# Power.net
KiCad netlist of a schematic drawn in Altium Designer
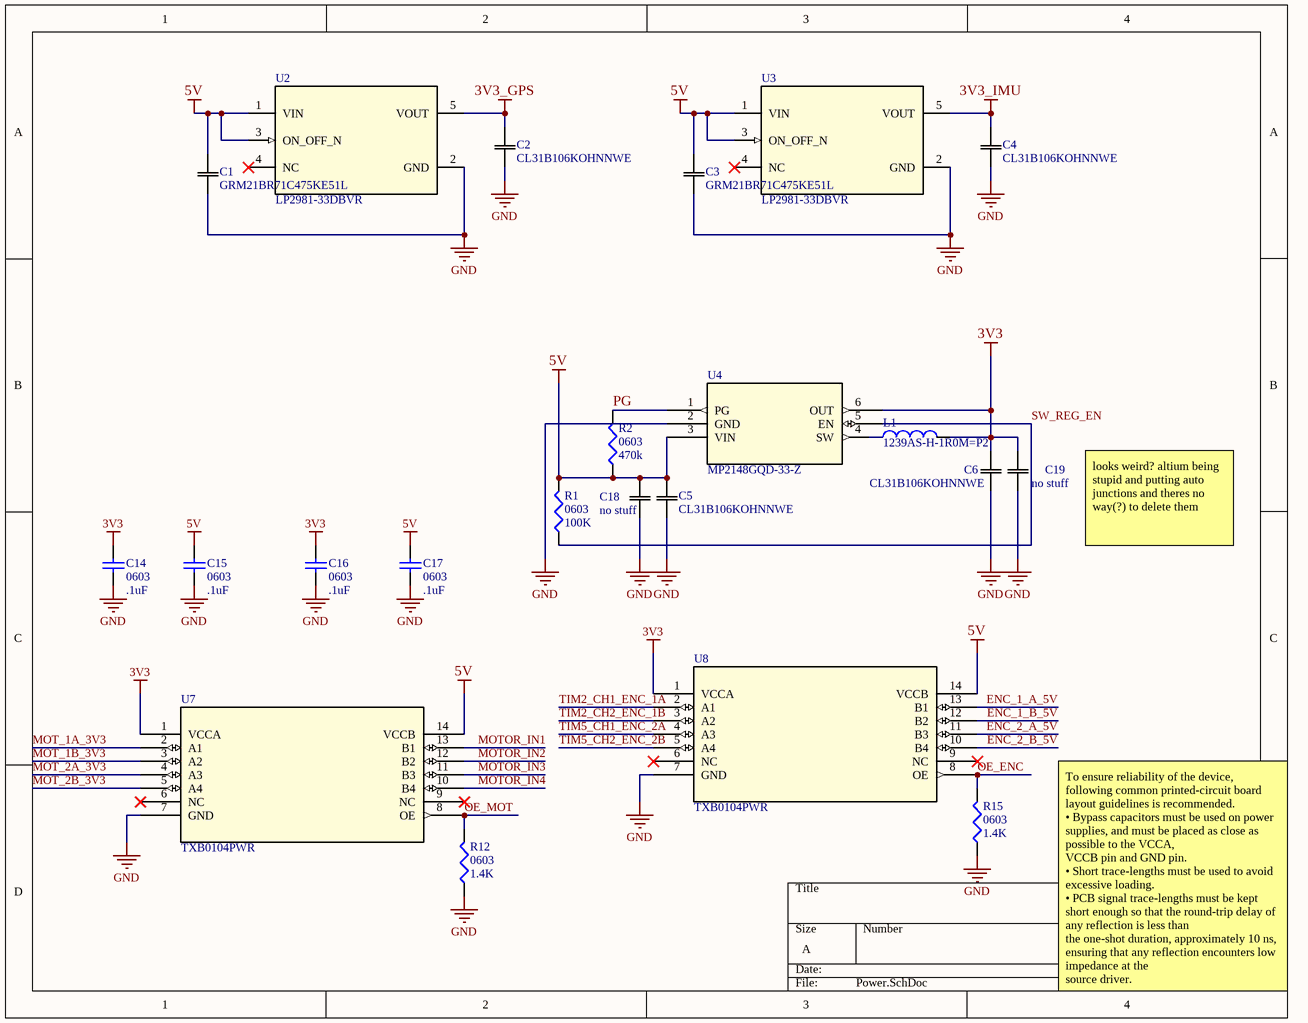
[diagram p0: Power.SchDoc]

(export (version "E")
  (design (tool "Eeschema 10.0.6"))
  (components
    (comp (ref "C1")
      (value "GRM21BR71C475KE51L")
      (footprint "swarm_crawler_pcb:CAP_GRM0805_2X1P25_MUR")
      (description "No Description Available")
      (fields (field (name "COPYRIGHT") "Copyright (C) 2023 Ultra Librarian. All rights reserved."))
      (libsource (lib "swarm_crawler_sch") (part "GRM21BR71C475KE51L"))
    )
    (comp (ref "C2")
      (value "CL31B106KOHNNWE")
      (footprint "swarm_crawler_pcb:CAP_CL31_SAM")
      (description "No Description Available")
      (fields (field (name "COPYRIGHT") "Copyright (C) 2023 Ultra Librarian. All rights reserved."))
      (libsource (lib "swarm_crawler_sch") (part "CL31B106KOHNNWE"))
    )
    (comp (ref "C3")
      (value "GRM21BR71C475KE51L")
      (footprint "swarm_crawler_pcb:CAP_GRM0805_2X1P25_MUR")
      (description "No Description Available")
      (fields (field (name "COPYRIGHT") "Copyright (C) 2023 Ultra Librarian. All rights reserved."))
      (libsource (lib "swarm_crawler_sch") (part "GRM21BR71C475KE51L"))
    )
    (comp (ref "C4")
      (value "CL31B106KOHNNWE")
      (footprint "swarm_crawler_pcb:CAP_CL31_SAM")
      (description "No Description Available")
      (fields (field (name "COPYRIGHT") "Copyright (C) 2023 Ultra Librarian. All rights reserved."))
      (libsource (lib "swarm_crawler_sch") (part "CL31B106KOHNNWE"))
    )
    (comp (ref "C5")
      (value "CL31B106KOHNNWE")
      (footprint "swarm_crawler_pcb:CAP_CL31_SAM")
      (description "No Description Available")
      (fields (field (name "COPYRIGHT") "Copyright (C) 2023 Ultra Librarian. All rights reserved."))
      (libsource (lib "swarm_crawler_sch") (part "CL31B106KOHNNWE"))
    )
    (comp (ref "C6")
      (value "CL31B106KOHNNWE")
      (footprint "swarm_crawler_pcb:CAP_CL31_SAM")
      (description "No Description Available")
      (fields (field (name "COPYRIGHT") "Copyright (C) 2023 Ultra Librarian. All rights reserved."))
      (libsource (lib "swarm_crawler_sch") (part "CL31B106KOHNNWE"))
    )
    (comp (ref "C14")
      (value "0603")
      (footprint "1608[0603]")
      (description "Capacitor (Semiconductor SIM Model)")
      (fields (field (name "ALTIUM_VALUE") ".1uF") (field (name "PUBLISHER") "Altium Limited"))
      (libsource (lib "Miscellaneous Devices") (part "Cap Semi"))
    )
    (comp (ref "C15")
      (value "0603")
      (footprint "1608[0603]")
      (description "Capacitor (Semiconductor SIM Model)")
      (fields (field (name "ALTIUM_VALUE") ".1uF") (field (name "PUBLISHER") "Altium Limited"))
      (libsource (lib "Miscellaneous Devices") (part "Cap Semi"))
    )
    (comp (ref "C16")
      (value "0603")
      (footprint "1608[0603]")
      (description "Capacitor (Semiconductor SIM Model)")
      (fields (field (name "ALTIUM_VALUE") ".1uF") (field (name "PUBLISHER") "Altium Limited"))
      (libsource (lib "Miscellaneous Devices") (part "Cap Semi"))
    )
    (comp (ref "C17")
      (value "0603")
      (footprint "1608[0603]")
      (description "Capacitor (Semiconductor SIM Model)")
      (fields (field (name "ALTIUM_VALUE") ".1uF") (field (name "PUBLISHER") "Altium Limited"))
      (libsource (lib "Miscellaneous Devices") (part "Cap Semi"))
    )
    (comp (ref "C18")
      (value "no stuff")
      (footprint "swarm_crawler_pcb:CAP_CL31_SAM")
      (description "No Description Available")
      (fields
        (field (name "MANUFACTURER_PART_NUMBER") "CL31B106KOHNNWE")
        (field (name "COPYRIGHT") "Copyright (C) 2023 Ultra Librarian. All rights reserved.")
      )
      (libsource (lib "swarm_crawler_sch") (part "CL31B106KOHNNWE"))
    )
    (comp (ref "C19")
      (value "no stuff")
      (footprint "swarm_crawler_pcb:CAP_CL31_SAM")
      (description "No Description Available")
      (fields
        (field (name "MANUFACTURER_PART_NUMBER") "CL31B106KOHNNWE")
        (field (name "COPYRIGHT") "Copyright (C) 2023 Ultra Librarian. All rights reserved.")
      )
      (libsource (lib "swarm_crawler_sch") (part "CL31B106KOHNNWE"))
    )
    (comp (ref "L1")
      (value "1239AS-H-1R0M=P2")
      (footprint "swarm_crawler_pcb:CAPC10555_55N_KEM")
      (description "Inductor with Inductance: 1uH Tol. +/-20%, Package: 1008 _2520_")
      (fields (field (name "DIGI-KEY_PART_NUMBER") "490-10564-1-ND") (field (name "MF") "Murata Electronics"))
      (libsource (lib "swarm_crawler_sch") (part "1239AS-H-1R0M=P2"))
    )
    (comp (ref "R1")
      (value "0603")
      (footprint "J1-0603")
      (description "Resistor")
      (fields (field (name "ALTIUM_VALUE") "100K") (field (name "PUBLISHER") "Altium Limited"))
      (libsource (lib "Miscellaneous Devices") (part "Res3"))
    )
    (comp (ref "R2")
      (value "0603")
      (footprint "J1-0603")
      (description "Resistor")
      (fields (field (name "ALTIUM_VALUE") "470k") (field (name "PUBLISHER") "Altium Limited"))
      (libsource (lib "Miscellaneous Devices") (part "Res3"))
    )
    (comp (ref "R12")
      (value "0603")
      (footprint "J1-0603")
      (description "Resistor")
      (fields (field (name "ALTIUM_VALUE") "1.4K") (field (name "PUBLISHER") "Altium Limited"))
      (libsource (lib "Miscellaneous Devices") (part "Res3"))
    )
    (comp (ref "R15")
      (value "0603")
      (footprint "J1-0603")
      (description "Resistor")
      (fields (field (name "ALTIUM_VALUE") "1.4K") (field (name "PUBLISHER") "Altium Limited"))
      (libsource (lib "Miscellaneous Devices") (part "Res3"))
    )
    (comp (ref "U2")
      (value "LP2981-33DBVR")
      (footprint "swarm_crawler_pcb:DBV0005A_N")
      (description "No Description Available")
      (fields (field (name "COPYRIGHT") "Copyright (C) 2023 Ultra Librarian. All rights reserved."))
      (libsource (lib "swarm_crawler_sch") (part "LP2981-33DBVR"))
    )
    (comp (ref "U3")
      (value "LP2981-33DBVR")
      (footprint "swarm_crawler_pcb:DBV0005A_N")
      (description "No Description Available")
      (fields (field (name "COPYRIGHT") "Copyright (C) 2023 Ultra Librarian. All rights reserved."))
      (libsource (lib "swarm_crawler_sch") (part "LP2981-33DBVR"))
    )
    (comp (ref "U4")
      (value "MP2148GQD-33-Z")
      (footprint "swarm_crawler_pcb:QFN-1p0x1p5_MNP")
      (description "No Description Available")
      (fields (field (name "COPYRIGHT") "Copyright (C) 2023 Ultra Librarian. All rights reserved."))
      (libsource (lib "swarm_crawler_sch") (part "MP2148GQD-33-Z"))
    )
    (comp (ref "U7")
      (value "TXB0104PWR")
      (footprint "swarm_crawler_pcb:PW14")
      (description "No Description Available")
      (fields (field (name "COPYRIGHT") "Copyright (C) 2023 Ultra Librarian. All rights reserved."))
      (libsource (lib "swarm_crawler_sch") (part "TXB0104PWR"))
    )
    (comp (ref "U8")
      (value "TXB0104PWR")
      (footprint "swarm_crawler_pcb:PW14")
      (description "No Description Available")
      (fields (field (name "COPYRIGHT") "Copyright (C) 2023 Ultra Librarian. All rights reserved."))
      (libsource (lib "swarm_crawler_sch") (part "TXB0104PWR"))
    )
  )
  (nets
    (net (code "1") (name "/ENC_1_A_5V") (class "Default")
      (node (ref "U8") (pin "13") (pinfunction "B1_13") (pintype "bidirectional"))
    )
    (net (code "2") (name "/ENC_1_B_5V") (class "Default")
      (node (ref "U8") (pin "12") (pinfunction "B2_12") (pintype "bidirectional"))
    )
    (net (code "3") (name "/ENC_2_A_5V") (class "Default")
      (node (ref "U8") (pin "11") (pinfunction "B3_11") (pintype "bidirectional"))
    )
    (net (code "4") (name "/ENC_2_B_5V") (class "Default")
      (node (ref "U8") (pin "10") (pinfunction "B4_10") (pintype "bidirectional"))
    )
    (net (code "5") (name "/MOTOR_IN1") (class "Default")
      (node (ref "U7") (pin "13") (pinfunction "B1_13") (pintype "bidirectional"))
    )
    (net (code "6") (name "/MOTOR_IN2") (class "Default")
      (node (ref "U7") (pin "12") (pinfunction "B2_12") (pintype "bidirectional"))
    )
    (net (code "7") (name "/MOTOR_IN3") (class "Default")
      (node (ref "U7") (pin "11") (pinfunction "B3_11") (pintype "bidirectional"))
    )
    (net (code "8") (name "/MOTOR_IN4") (class "Default")
      (node (ref "U7") (pin "10") (pinfunction "B4_10") (pintype "bidirectional"))
    )
    (net (code "9") (name "/MOT_1A_3V3") (class "Default")
      (node (ref "U7") (pin "2") (pinfunction "A1_2") (pintype "bidirectional"))
    )
    (net (code "10") (name "/MOT_1B_3V3") (class "Default")
      (node (ref "U7") (pin "3") (pinfunction "A2_3") (pintype "bidirectional"))
    )
    (net (code "11") (name "/MOT_2A_3V3") (class "Default")
      (node (ref "U7") (pin "4") (pinfunction "A3_4") (pintype "bidirectional"))
    )
    (net (code "12") (name "/MOT_2B_3V3") (class "Default")
      (node (ref "U7") (pin "5") (pinfunction "A4_5") (pintype "bidirectional"))
    )
    (net (code "13") (name "/OE_ENC") (class "Default")
      (node (ref "R15") (pin "2") (pinfunction "2_2") (pintype "passive"))
      (node (ref "U8") (pin "8") (pinfunction "OE_8") (pintype "output"))
    )
    (net (code "14") (name "/OE_MOT") (class "Default")
      (node (ref "R12") (pin "2") (pinfunction "2_2") (pintype "passive"))
      (node (ref "U7") (pin "8") (pinfunction "OE_8") (pintype "output"))
    )
    (net (code "15") (name "/PG") (class "Default")
      (node (ref "R2") (pin "2") (pinfunction "2_2") (pintype "passive"))
      (node (ref "U4") (pin "1") (pinfunction "PG_1") (pintype "output"))
    )
    (net (code "16") (name "/SW_REG_EN") (class "Default")
      (node (ref "R1") (pin "1") (pinfunction "1_1") (pintype "passive"))
      (node (ref "U4") (pin "5") (pinfunction "EN_5") (pintype "bidirectional"))
    )
    (net (code "17") (name "/TIM2_CH1_ENC_1A") (class "Default")
      (node (ref "U8") (pin "2") (pinfunction "A1_2") (pintype "bidirectional"))
    )
    (net (code "18") (name "/TIM2_CH2_ENC_1B") (class "Default")
      (node (ref "U8") (pin "3") (pinfunction "A2_3") (pintype "bidirectional"))
    )
    (net (code "19") (name "/TIM5_CH1_ENC_2A") (class "Default")
      (node (ref "U8") (pin "4") (pinfunction "A3_4") (pintype "bidirectional"))
    )
    (net (code "20") (name "/TIM5_CH2_ENC_2B") (class "Default")
      (node (ref "U8") (pin "5") (pinfunction "A4_5") (pintype "bidirectional"))
    )
    (net (code "21") (name "3V3") (class "Default")
      (node (ref "C14") (pin "2") (pinfunction "2_2") (pintype "passive"))
      (node (ref "C16") (pin "2") (pinfunction "2_2") (pintype "passive"))
      (node (ref "C19") (pin "2") (pinfunction "2_2") (pintype "passive"))
      (node (ref "C6") (pin "2") (pinfunction "2_2") (pintype "passive"))
      (node (ref "L1") (pin "2") (pinfunction "2_2") (pintype "passive"))
      (node (ref "U4") (pin "6") (pinfunction "OUT_6") (pintype "output"))
      (node (ref "U7") (pin "1") (pinfunction "VCCA_1") (pintype "power_in"))
      (node (ref "U8") (pin "1") (pinfunction "VCCA_1") (pintype "power_in"))
    )
    (net (code "22") (name "3V3_GPS") (class "Default")
      (node (ref "C2") (pin "2") (pinfunction "2_2") (pintype "passive"))
      (node (ref "U2") (pin "5") (pinfunction "VOUT_5") (pintype "power_in"))
    )
    (net (code "23") (name "3V3_IMU") (class "Default")
      (node (ref "C4") (pin "2") (pinfunction "2_2") (pintype "passive"))
      (node (ref "U3") (pin "5") (pinfunction "VOUT_5") (pintype "power_in"))
    )
    (net (code "24") (name "5V") (class "Default")
      (node (ref "C1") (pin "2") (pinfunction "2_2") (pintype "passive"))
      (node (ref "C15") (pin "2") (pinfunction "2_2") (pintype "passive"))
      (node (ref "C17") (pin "2") (pinfunction "2_2") (pintype "passive"))
      (node (ref "C18") (pin "2") (pinfunction "2_2") (pintype "passive"))
      (node (ref "C3") (pin "2") (pinfunction "2_2") (pintype "passive"))
      (node (ref "C5") (pin "2") (pinfunction "2_2") (pintype "passive"))
      (node (ref "R1") (pin "2") (pinfunction "2_2") (pintype "passive"))
      (node (ref "R2") (pin "1") (pinfunction "1_1") (pintype "passive"))
      (node (ref "U2") (pin "1") (pinfunction "VIN_1") (pintype "power_in"))
      (node (ref "U2") (pin "3") (pinfunction "ON_OFF_N_3") (pintype "input"))
      (node (ref "U3") (pin "1") (pinfunction "VIN_1") (pintype "power_in"))
      (node (ref "U3") (pin "3") (pinfunction "ON_OFF_N_3") (pintype "input"))
      (node (ref "U4") (pin "3") (pinfunction "VIN_3") (pintype "power_in"))
      (node (ref "U7") (pin "14") (pinfunction "VCCB_14") (pintype "power_in"))
      (node (ref "U8") (pin "14") (pinfunction "VCCB_14") (pintype "power_in"))
    )
    (net (code "25") (name "GND") (class "Default")
      (node (ref "C1") (pin "1") (pinfunction "1_1") (pintype "passive"))
      (node (ref "C14") (pin "1") (pinfunction "1_1") (pintype "passive"))
      (node (ref "C15") (pin "1") (pinfunction "1_1") (pintype "passive"))
      (node (ref "C16") (pin "1") (pinfunction "1_1") (pintype "passive"))
      (node (ref "C17") (pin "1") (pinfunction "1_1") (pintype "passive"))
      (node (ref "C18") (pin "1") (pinfunction "1_1") (pintype "passive"))
      (node (ref "C19") (pin "1") (pinfunction "1_1") (pintype "passive"))
      (node (ref "C2") (pin "1") (pinfunction "1_1") (pintype "passive"))
      (node (ref "C3") (pin "1") (pinfunction "1_1") (pintype "passive"))
      (node (ref "C4") (pin "1") (pinfunction "1_1") (pintype "passive"))
      (node (ref "C5") (pin "1") (pinfunction "1_1") (pintype "passive"))
      (node (ref "C6") (pin "1") (pinfunction "1_1") (pintype "passive"))
      (node (ref "R12") (pin "1") (pinfunction "1_1") (pintype "passive"))
      (node (ref "R15") (pin "1") (pinfunction "1_1") (pintype "passive"))
      (node (ref "U2") (pin "2") (pinfunction "GND_2") (pintype "power_in"))
      (node (ref "U3") (pin "2") (pinfunction "GND_2") (pintype "power_in"))
      (node (ref "U4") (pin "2") (pinfunction "GND_2") (pintype "passive"))
      (node (ref "U7") (pin "7") (pinfunction "GND_7") (pintype "power_in"))
      (node (ref "U8") (pin "7") (pinfunction "GND_7") (pintype "power_in"))
    )
    (net (code "26") (name "Net-(U4-SW)") (class "Default")
      (node (ref "L1") (pin "1") (pinfunction "1_1") (pintype "passive"))
      (node (ref "U4") (pin "4") (pinfunction "SW_4") (pintype "output"))
    )
    (net (code "27") (name "unconnected-(U2-NC-Pad4)") (class "Default")
      (node (ref "U2") (pin "4") (pinfunction "NC_4") (pintype "passive+no_connect"))
    )
    (net (code "28") (name "unconnected-(U3-NC-Pad4)") (class "Default")
      (node (ref "U3") (pin "4") (pinfunction "NC_4") (pintype "passive+no_connect"))
    )
    (net (code "29") (name "unconnected-(U7-NC-Pad6)") (class "Default")
      (node (ref "U7") (pin "6") (pinfunction "NC_6") (pintype "passive+no_connect"))
    )
    (net (code "30") (name "unconnected-(U7-NC-Pad9)") (class "Default")
      (node (ref "U7") (pin "9") (pinfunction "NC_9") (pintype "passive+no_connect"))
    )
    (net (code "31") (name "unconnected-(U8-NC-Pad6)") (class "Default")
      (node (ref "U8") (pin "6") (pinfunction "NC_6") (pintype "passive+no_connect"))
    )
    (net (code "32") (name "unconnected-(U8-NC-Pad9)") (class "Default")
      (node (ref "U8") (pin "9") (pinfunction "NC_9") (pintype "passive+no_connect"))
    )
  )
)
